# single_varactor.net
KiCad netlist of a schematic drawn in EAGLE
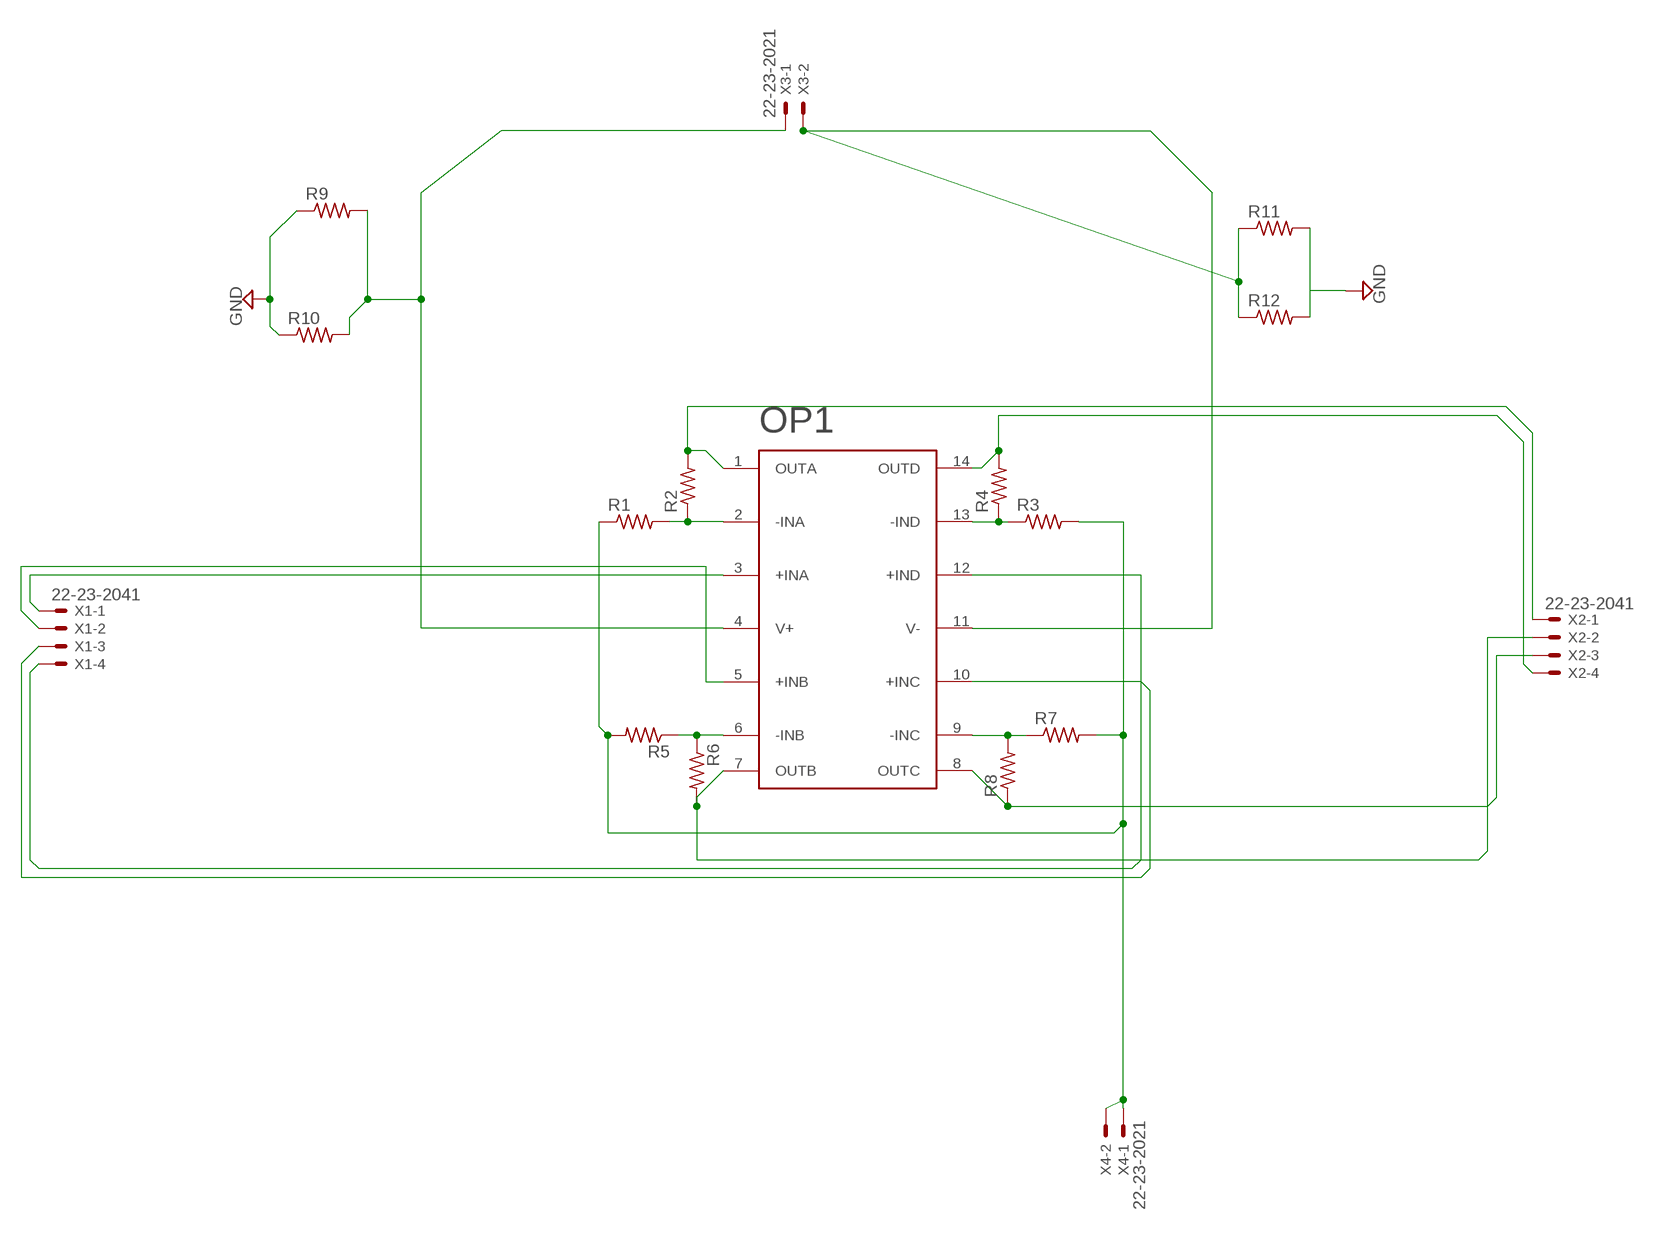
[diagram p0: schematic, sheet 1]

(export (version "E")
  (design (tool "Eeschema 10.0.6"))
  (components
    (comp (ref "OP1")
      (value "OPAX4172")
      (footprint "eagle-import:OPAX172")
      (libsource (lib "eagle-import") (part "OPAX4172"))
    )
    (comp (ref "R1")
      (value "R-US_0204/2V")
      (footprint "eagle-import:0204V")
      (libsource (lib "eagle-import") (part "R-US_0204/2V"))
    )
    (comp (ref "R2")
      (value "R-US_0204/2V")
      (footprint "eagle-import:0204V")
      (libsource (lib "eagle-import") (part "R-US_0204/2V"))
    )
    (comp (ref "R3")
      (value "R-US_0204/2V")
      (footprint "eagle-import:0204V")
      (libsource (lib "eagle-import") (part "R-US_0204/2V"))
    )
    (comp (ref "R4")
      (value "R-US_0204/2V")
      (footprint "eagle-import:0204V")
      (libsource (lib "eagle-import") (part "R-US_0204/2V"))
    )
    (comp (ref "R5")
      (value "R-US_0204/2V")
      (footprint "eagle-import:0204V")
      (libsource (lib "eagle-import") (part "R-US_0204/2V"))
    )
    (comp (ref "R6")
      (value "R-US_0204/2V")
      (footprint "eagle-import:0204V")
      (libsource (lib "eagle-import") (part "R-US_0204/2V"))
    )
    (comp (ref "R7")
      (value "R-US_0204/2V")
      (footprint "eagle-import:0204V")
      (libsource (lib "eagle-import") (part "R-US_0204/2V"))
    )
    (comp (ref "R8")
      (value "R-US_0204/2V")
      (footprint "eagle-import:0204V")
      (libsource (lib "eagle-import") (part "R-US_0204/2V"))
    )
    (comp (ref "R9")
      (value "R-US_0204/2V")
      (footprint "eagle-import:0204V")
      (libsource (lib "eagle-import") (part "R-US_0204/2V"))
    )
    (comp (ref "R10")
      (value "R-US_0204/2V")
      (footprint "eagle-import:0204V")
      (libsource (lib "eagle-import") (part "R-US_0204/2V"))
    )
    (comp (ref "R11")
      (value "R-US_0204/2V")
      (footprint "eagle-import:0204V")
      (libsource (lib "eagle-import") (part "R-US_0204/2V"))
    )
    (comp (ref "R12")
      (value "R-US_0204/2V")
      (footprint "eagle-import:0204V")
      (libsource (lib "eagle-import") (part "R-US_0204/2V"))
    )
    (comp (ref "X1")
      (value "22-23-2041")
      (footprint "eagle-import:22-23-2041")
      (fields (field (name "MF") "MOLEX"))
      (libsource (lib "eagle-import") (part "22-23-2041"))
    )
    (comp (ref "X2")
      (value "22-23-2041")
      (footprint "eagle-import:22-23-2041")
      (fields (field (name "MF") "MOLEX"))
      (libsource (lib "eagle-import") (part "22-23-2041"))
    )
    (comp (ref "X3")
      (value "22-23-2021")
      (footprint "eagle-import:22-23-2021")
      (fields (field (name "MF") "MOLEX"))
      (libsource (lib "eagle-import") (part "22-23-2021"))
    )
    (comp (ref "X4")
      (value "22-23-2021")
      (footprint "eagle-import:22-23-2021")
      (fields (field (name "MF") "MOLEX"))
      (libsource (lib "eagle-import") (part "22-23-2021"))
    )
  )
  (nets
    (net (code "1") (name "GND") (class "Default")
      (node (ref "R10") (pin "1") (pinfunction "1_1") (pintype "passive"))
      (node (ref "R9") (pin "1") (pinfunction "1_1") (pintype "passive"))
    )
    (net (code "2") (name "Net-(OP1-+INA)") (class "Default")
      (node (ref "OP1") (pin "3") (pinfunction "+INA_3") (pintype "bidirectional"))
      (node (ref "X1") (pin "1") (pinfunction "S_1") (pintype "passive"))
    )
    (net (code "3") (name "Net-(OP1-+INB)") (class "Default")
      (node (ref "OP1") (pin "5") (pinfunction "+INB_5") (pintype "bidirectional"))
      (node (ref "X1") (pin "2") (pinfunction "S_2") (pintype "passive"))
    )
    (net (code "4") (name "Net-(OP1-+INC)") (class "Default")
      (node (ref "OP1") (pin "10") (pinfunction "+INC_10") (pintype "bidirectional"))
      (node (ref "X1") (pin "3") (pinfunction "S_3") (pintype "passive"))
    )
    (net (code "5") (name "Net-(OP1-+IND)") (class "Default")
      (node (ref "OP1") (pin "12") (pinfunction "+IND_12") (pintype "bidirectional"))
      (node (ref "X1") (pin "4") (pinfunction "S_4") (pintype "passive"))
    )
    (net (code "6") (name "Net-(OP1--INA)") (class "Default")
      (node (ref "OP1") (pin "2") (pinfunction "-INA_2") (pintype "bidirectional"))
      (node (ref "R1") (pin "2") (pinfunction "2_2") (pintype "passive"))
      (node (ref "R2") (pin "1") (pinfunction "1_1") (pintype "passive"))
    )
    (net (code "7") (name "Net-(OP1--INB)") (class "Default")
      (node (ref "OP1") (pin "6") (pinfunction "-INB_6") (pintype "bidirectional"))
      (node (ref "R5") (pin "1") (pinfunction "1_1") (pintype "passive"))
      (node (ref "R6") (pin "1") (pinfunction "1_1") (pintype "passive"))
    )
    (net (code "8") (name "Net-(OP1--INC)") (class "Default")
      (node (ref "OP1") (pin "9") (pinfunction "-INC_9") (pintype "bidirectional"))
      (node (ref "R7") (pin "1") (pinfunction "1_1") (pintype "passive"))
      (node (ref "R8") (pin "2") (pinfunction "2_2") (pintype "passive"))
    )
    (net (code "9") (name "Net-(OP1--IND)") (class "Default")
      (node (ref "OP1") (pin "13") (pinfunction "-IND_13") (pintype "bidirectional"))
      (node (ref "R3") (pin "1") (pinfunction "1_1") (pintype "passive"))
      (node (ref "R4") (pin "1") (pinfunction "1_1") (pintype "passive"))
    )
    (net (code "10") (name "Net-(OP1-OUTA)") (class "Default")
      (node (ref "OP1") (pin "1") (pinfunction "OUTA_1") (pintype "bidirectional"))
      (node (ref "R2") (pin "2") (pinfunction "2_2") (pintype "passive"))
      (node (ref "X2") (pin "1") (pinfunction "S_1") (pintype "passive"))
    )
    (net (code "11") (name "Net-(OP1-OUTB)") (class "Default")
      (node (ref "OP1") (pin "7") (pinfunction "OUTB_7") (pintype "bidirectional"))
      (node (ref "R6") (pin "2") (pinfunction "2_2") (pintype "passive"))
      (node (ref "X2") (pin "2") (pinfunction "S_2") (pintype "passive"))
    )
    (net (code "12") (name "Net-(OP1-OUTC)") (class "Default")
      (node (ref "OP1") (pin "8") (pinfunction "OUTC_8") (pintype "bidirectional"))
      (node (ref "R8") (pin "1") (pinfunction "1_1") (pintype "passive"))
      (node (ref "X2") (pin "3") (pinfunction "S_3") (pintype "passive"))
    )
    (net (code "13") (name "Net-(OP1-OUTD)") (class "Default")
      (node (ref "OP1") (pin "14") (pinfunction "OUTD_14") (pintype "bidirectional"))
      (node (ref "R4") (pin "2") (pinfunction "2_2") (pintype "passive"))
      (node (ref "X2") (pin "4") (pinfunction "S_4") (pintype "passive"))
    )
    (net (code "14") (name "Net-(OP1-V+)") (class "Default")
      (node (ref "OP1") (pin "4") (pinfunction "V+_4") (pintype "bidirectional"))
      (node (ref "R10") (pin "2") (pinfunction "2_2") (pintype "passive"))
      (node (ref "R9") (pin "2") (pinfunction "2_2") (pintype "passive"))
      (node (ref "X3") (pin "1") (pinfunction "S_1") (pintype "passive"))
    )
    (net (code "15") (name "Net-(OP1-V-)") (class "Default")
      (node (ref "OP1") (pin "11") (pinfunction "V-_11") (pintype "bidirectional"))
      (node (ref "R11") (pin "1") (pinfunction "1_1") (pintype "passive"))
      (node (ref "R12") (pin "1") (pinfunction "1_1") (pintype "passive"))
      (node (ref "X3") (pin "2") (pinfunction "S_2") (pintype "passive"))
    )
    (net (code "16") (name "Net-(R11-Pad2)") (class "Default")
      (node (ref "R11") (pin "2") (pinfunction "2_2") (pintype "passive"))
      (node (ref "R12") (pin "2") (pinfunction "2_2") (pintype "passive"))
    )
    (net (code "17") (name "Net-(X4A-S)") (class "Default")
      (node (ref "R1") (pin "1") (pinfunction "1_1") (pintype "passive"))
      (node (ref "R3") (pin "2") (pinfunction "2_2") (pintype "passive"))
      (node (ref "R5") (pin "2") (pinfunction "2_2") (pintype "passive"))
      (node (ref "R7") (pin "2") (pinfunction "2_2") (pintype "passive"))
      (node (ref "X4") (pin "1") (pinfunction "S_1") (pintype "passive"))
      (node (ref "X4") (pin "2") (pinfunction "S_2") (pintype "passive"))
    )
  )
)
